# Sheet1.net
KiCad netlist of a schematic drawn in Altium Designer
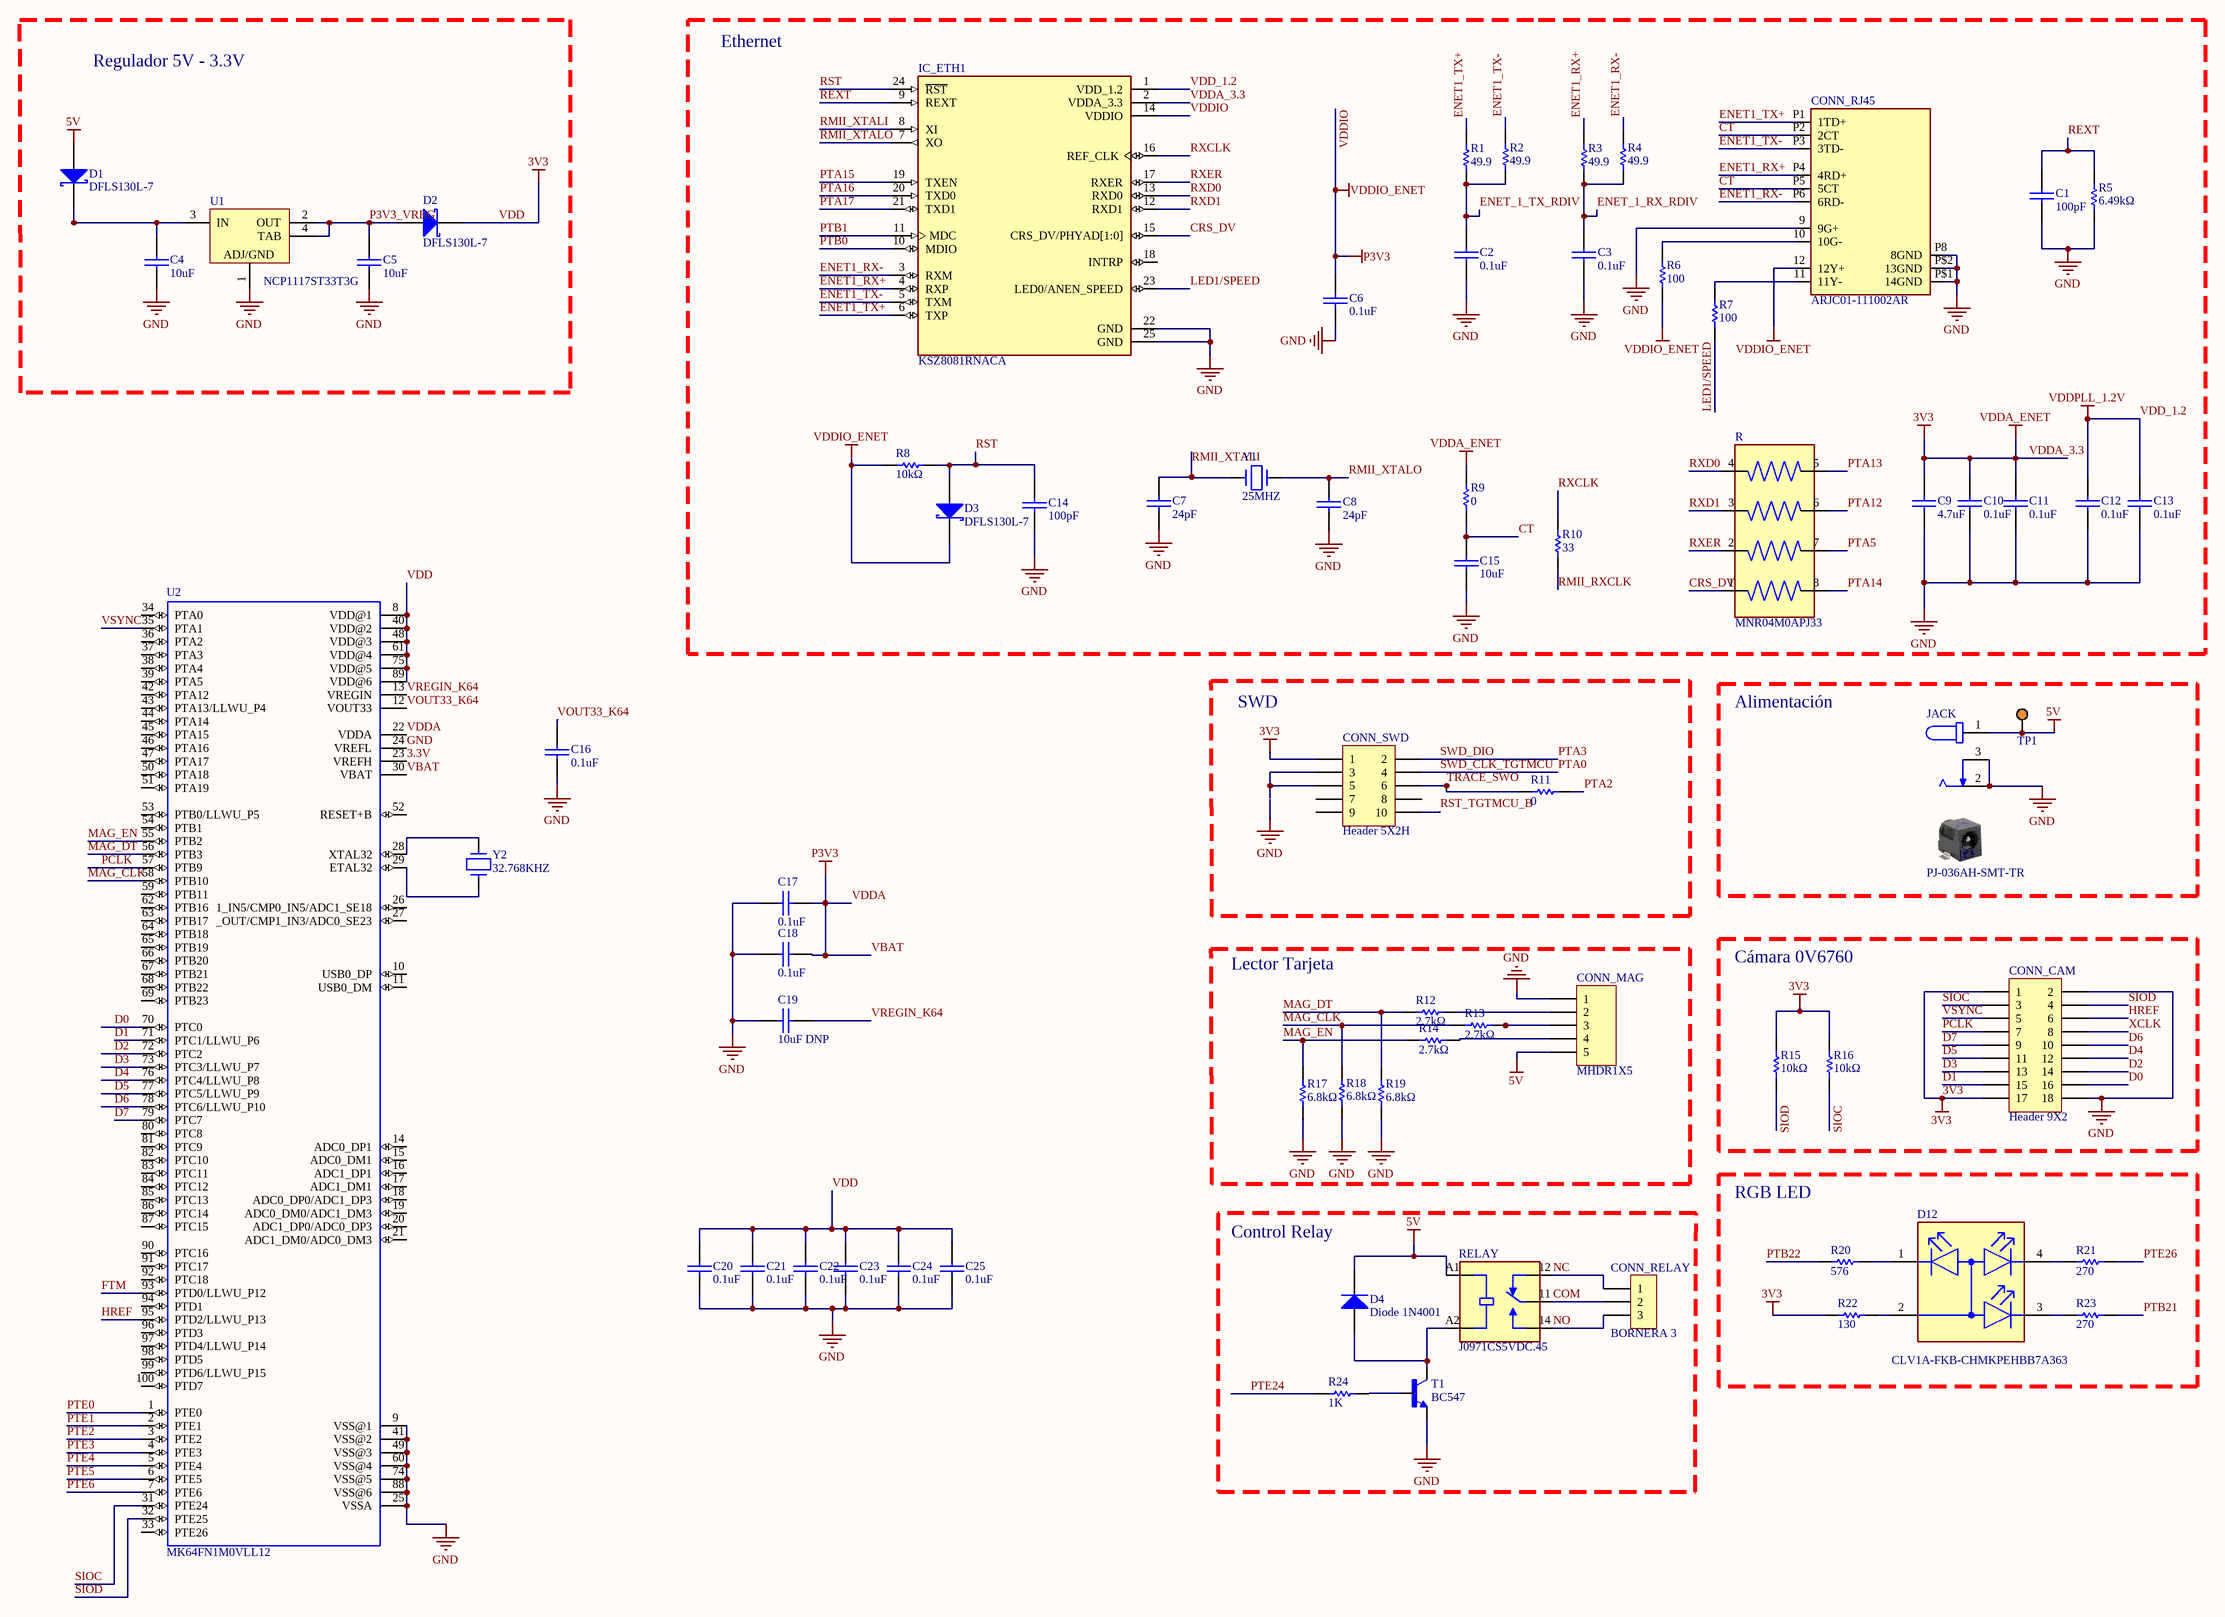
[diagram p0: Sheet1.SchDoc]

(export (version "E")
  (design (tool "Eeschema 10.0.6"))
  (components
    (comp (ref "C1") (value "100pF") (footprint "0805") (libsource (lib "Schematics") (part "CAP")))
    (comp (ref "C2") (value "0.1uF") (footprint "0805") (libsource (lib "Schematics") (part "CAP")))
    (comp (ref "C3") (value "0.1uF") (footprint "0805") (libsource (lib "Schematics") (part "CAP")))
    (comp (ref "C4") (value "10uF") (footprint "0805") (libsource (lib "Schematics") (part "CAP")))
    (comp (ref "C5") (value "10uF") (footprint "0805") (libsource (lib "Schematics") (part "CAP")))
    (comp (ref "C6") (value "0.1uF") (footprint "0805") (libsource (lib "Schematics") (part "CAP")))
    (comp (ref "C7") (value "24pF") (footprint "0805") (libsource (lib "Schematics") (part "CAP")))
    (comp (ref "C8") (value "24pF") (footprint "0805") (libsource (lib "Schematics") (part "CAP")))
    (comp (ref "C9") (value "4.7uF") (footprint "0805") (libsource (lib "Schematics") (part "CAP")))
    (comp (ref "C10") (value "0.1uF") (footprint "0805") (libsource (lib "Schematics") (part "CAP")))
    (comp (ref "C11") (value "0.1uF") (footprint "0805") (libsource (lib "Schematics") (part "CAP")))
    (comp (ref "C12") (value "0.1uF") (footprint "0805") (libsource (lib "Schematics") (part "CAP")))
    (comp (ref "C13") (value "0.1uF") (footprint "0805") (libsource (lib "Schematics") (part "CAP")))
    (comp (ref "C14") (value "100pF") (footprint "0805") (libsource (lib "Schematics") (part "CAP")))
    (comp (ref "C15") (value "10uF") (footprint "0805") (libsource (lib "Schematics") (part "CAP")))
    (comp (ref "C16") (value "0.1uF") (footprint "1206") (libsource (lib "Schematics") (part "CAP")))
    (comp (ref "C17") (value "0.1uF") (footprint "0805") (libsource (lib "Schematics") (part "CAP")))
    (comp (ref "C18") (value "0.1uF") (footprint "0805") (libsource (lib "Schematics") (part "CAP")))
    (comp (ref "C19") (value "10uF DNP") (footprint "1206") (libsource (lib "Schematics") (part "CAP")))
    (comp (ref "C20") (value "0.1uF") (footprint "0805") (libsource (lib "Schematics") (part "CAP")))
    (comp (ref "C21") (value "0.1uF") (footprint "0805") (libsource (lib "Schematics") (part "CAP")))
    (comp (ref "C22") (value "0.1uF") (footprint "0805") (libsource (lib "Schematics") (part "CAP")))
    (comp (ref "C23") (value "0.1uF") (footprint "0805") (libsource (lib "Schematics") (part "CAP")))
    (comp (ref "C24") (value "0.1uF") (footprint "0805") (libsource (lib "Schematics") (part "CAP")))
    (comp (ref "C25") (value "0.1uF") (footprint "0805") (libsource (lib "Schematics") (part "CAP")))
    (comp (ref "CONN_CAM")
      (value "Header 9X2")
      (footprint "HDR2X9")
      (description "Header, 9-Pin, Dual row")
      (fields (field (name "PUBLISHER") "Altium Limited"))
      (libsource (lib "Miscellaneous Connectors") (part "Header 9X2"))
    )
    (comp (ref "CONN_MAG")
      (value "MHDR1X5")
      (footprint "MHDR1X5")
      (description "Header, 5-Pin")
      (fields (field (name "PUBLISHER") "Altium Limited"))
      (libsource (lib "Miscellaneous Connectors") (part "MHDR1X5"))
    )
    (comp (ref "CONN_RELAY")
      (value "BORNERA 3")
      (footprint "BORNERA3")
      (libsource (lib "Schematics") (part "BORNERA 3"))
    )
    (comp (ref "CONN_RJ45")
      (value "ARJC01-111002AR")
      (footprint "ARJC01-111002AR")
      (description "1 Port RJ45 Magjack Connector Through Hole 10/100 Base-TX, AutoMDIX")
      (fields (field (name "MF") "Abracon LLC"))
      (libsource (lib "ARJC01-111002AR") (part "ARJC01-111002AR"))
    )
    (comp (ref "CONN_SWD")
      (value "Header 5X2H")
      (footprint "HDR2X5H")
      (description "Header, 5-Pin, Dual row, Right Angle")
      (fields (field (name "PUBLISHER") "Altium Limited"))
      (libsource (lib "Miscellaneous Connectors") (part "Header 5X2H"))
    )
    (comp (ref "D1")
      (value "DFLS130L-7")
      (footprint "DIOD-POWERDI123-2_A_V")
      (description "Schottky Barrier Rectifier, 30 V, 1 A, -40 to 125 degC, 2-Pin SMD, RoHS, Tape and Reel")
      (fields (field (name "MANUFACTURER") "Diodes Inc"))
      (libsource (lib "Altium Content Vault") (part "DSKY-AK-2"))
    )
    (comp (ref "D2")
      (value "DFLS130L-7")
      (footprint "DIOD-POWERDI123-2_A_V")
      (description "Schottky Barrier Rectifier, 30 V, 1 A, -40 to 125 degC, 2-Pin SMD, RoHS, Tape and Reel")
      (fields (field (name "MANUFACTURER") "Diodes Inc"))
      (libsource (lib "Altium Content Vault") (part "DSKY-AK-2"))
    )
    (comp (ref "D3")
      (value "DFLS130L-7")
      (footprint "DIOD-POWERDI123-2_A_V")
      (description "Schottky Barrier Rectifier, 30 V, 1 A, -40 to 125 degC, 2-Pin SMD, RoHS, Tape and Reel")
      (fields (field (name "MANUFACTURER") "Diodes Inc"))
      (libsource (lib "Altium Content Vault") (part "DSKY-AK-2"))
    )
    (comp (ref "D4")
      (value "Diode 1N4001")
      (footprint "DO-41")
      (description "1 Amp General Purpose Rectifier")
      (fields (field (name "PUBLISHER") "Altium Limited"))
      (libsource (lib "Miscellaneous Devices") (part "Diode 1N4001"))
    )
    (comp (ref "D12")
      (value "CLV1A-FKB-CHMKPEHBB7A363")
      (footprint "FP-CLV1A-FKB-CHMKPEHBB7A3-MFG")
      (description "LED RGB 4PLCC SMD")
      (libsource (lib "Altium Content Vault") (part "37e83e7cb408f3cd33eae76522c4c17"))
    )
    (comp (ref "IC_ETH1")
      (value "KSZ8081RNACA")
      (footprint "QFN50P400X400X90-25N")
      (description "1/1 Transceiver Full RMII 24-QFN _4x4_")
      (fields (field (name "MF") "Microchip"))
      (libsource (lib "KSZ8081RNACA") (part "KSZ8081RNACA"))
    )
    (comp (ref "JACK")
      (value "CONN_JACKDC_SMD_PJ-036AH-SMT-TR")
      (footprint "CUI_PJ-036AH-SMT-TR")
      (description "CONN PWR JACK 2X5.5MM SOLDER")
      (fields
        (field (name "MANUFACTURER") "CUI Devices")
        (field (name "MANUFACTURER PART NUMBER") "PJ-036AH-SMT-TR")
      )
      (libsource (lib "NerveBox") (part "CONN_JACKDC_SMD_PJ-036AH-SMT-TR"))
    )
    (comp (ref "R")
      (value "MNR04M0APJ33")
      (footprint "RESCAXS50P200X100X45-8N")
      (description "Res Array 330K Ohm 5% Â±200ppm/Â°C ISOL Epoxy 8-Pin 0804(4 X 0402) Convex SMD Automotive T/R")
      (fields (field (name "MP") "MNR04M0APJ334") (field (name "MF") "Rohm"))
      (libsource (lib "MNR04M0APJ334") (part "MNR04M0APJ334"))
    )
    (comp (ref "R1") (value "49.9") (footprint "0805") (libsource (lib "Schematics") (part "RES")))
    (comp (ref "R2") (value "49.9") (footprint "0805") (libsource (lib "Schematics") (part "RES")))
    (comp (ref "R3") (value "49.9") (footprint "0805") (libsource (lib "Schematics") (part "RES")))
    (comp (ref "R4") (value "49.9") (footprint "0805") (libsource (lib "Schematics") (part "RES")))
    (comp (ref "R5")
      (value "RES_10k_SMD_RMCF0603FT10K0")
      (footprint "RES_0603")
      (description "RES 10K OHM 1% 1/10W 0603")
      (fields
        (field (name "MANUFACTURER PART NUMBER") "RMCF0603FT10K0")
        (field (name "MANUFACTURER") "Stackpole Electronics Inc")
        (field (name "POWER") "6.49kΩ")
      )
      (libsource (lib "NerveBox") (part "RES_10k_SMD_RMCF0603FT10K0"))
    )
    (comp (ref "R6") (value "100") (footprint "0805") (libsource (lib "Schematics") (part "RES")))
    (comp (ref "R7") (value "100") (footprint "0805") (libsource (lib "Schematics") (part "RES")))
    (comp (ref "R8")
      (value "RES_10k_SMD_RMCF0603FT10K0")
      (footprint "RES_0603")
      (description "RES 10K OHM 1% 1/10W 0603")
      (fields
        (field (name "MANUFACTURER PART NUMBER") "RMCF0603FT10K0")
        (field (name "MANUFACTURER") "Stackpole Electronics Inc")
        (field (name "POWER") "10kΩ")
      )
      (libsource (lib "NerveBox") (part "RES_10k_SMD_RMCF0603FT10K0"))
    )
    (comp (ref "R9") (value "0") (footprint "0805") (libsource (lib "Schematics") (part "RES")))
    (comp (ref "R10")
      (value "RES_10k_SMD_RMCF0603FT10K0")
      (footprint "RES_0603")
      (description "RES 10K OHM 1% 1/10W 0603")
      (fields
        (field (name "MANUFACTURER PART NUMBER") "RMCF0603FT10K0")
        (field (name "MANUFACTURER") "Stackpole Electronics Inc")
        (field (name "POWER") "33")
      )
      (libsource (lib "NerveBox") (part "RES_10k_SMD_RMCF0603FT10K0"))
    )
    (comp (ref "R11")
      (value "RES_10k_SMD_RMCF0603FT10K0")
      (footprint "RES_0603")
      (description "RES 10K OHM 1% 1/10W 0603")
      (fields
        (field (name "MANUFACTURER PART NUMBER") "RMCF0603FT10K0")
        (field (name "MANUFACTURER") "Stackpole Electronics Inc")
        (field (name "POWER") "0")
      )
      (libsource (lib "NerveBox") (part "RES_10k_SMD_RMCF0603FT10K0"))
    )
    (comp (ref "R12")
      (value "RES_10k_SMD_RMCF0603FT10K0")
      (footprint "RES_0603")
      (description "RES 10K OHM 1% 1/10W 0603")
      (fields
        (field (name "MANUFACTURER PART NUMBER") "RMCF0603FT10K0")
        (field (name "MANUFACTURER") "Stackpole Electronics Inc")
        (field (name "POWER") "2.7kΩ")
      )
      (libsource (lib "NerveBox") (part "RES_10k_SMD_RMCF0603FT10K0"))
    )
    (comp (ref "R13")
      (value "RES_10k_SMD_RMCF0603FT10K0")
      (footprint "RES_0603")
      (description "RES 10K OHM 1% 1/10W 0603")
      (fields
        (field (name "MANUFACTURER PART NUMBER") "RMCF0603FT10K0")
        (field (name "MANUFACTURER") "Stackpole Electronics Inc")
        (field (name "POWER") "2.7kΩ")
      )
      (libsource (lib "NerveBox") (part "RES_10k_SMD_RMCF0603FT10K0"))
    )
    (comp (ref "R14")
      (value "RES_10k_SMD_RMCF0603FT10K0")
      (footprint "RES_0603")
      (description "RES 10K OHM 1% 1/10W 0603")
      (fields
        (field (name "MANUFACTURER PART NUMBER") "RMCF0603FT10K0")
        (field (name "MANUFACTURER") "Stackpole Electronics Inc")
        (field (name "POWER") "2.7kΩ")
      )
      (libsource (lib "NerveBox") (part "RES_10k_SMD_RMCF0603FT10K0"))
    )
    (comp (ref "R15")
      (value "RES_10k_SMD_RMCF0603FT10K0")
      (footprint "RES_0603")
      (description "RES 10K OHM 1% 1/10W 0603")
      (fields
        (field (name "MANUFACTURER PART NUMBER") "RMCF0603FT10K0")
        (field (name "MANUFACTURER") "Stackpole Electronics Inc")
        (field (name "POWER") "10kΩ")
      )
      (libsource (lib "NerveBox") (part "RES_10k_SMD_RMCF0603FT10K0"))
    )
    (comp (ref "R16")
      (value "RES_10k_SMD_RMCF0603FT10K0")
      (footprint "RES_0603")
      (description "RES 10K OHM 1% 1/10W 0603")
      (fields
        (field (name "MANUFACTURER PART NUMBER") "RMCF0603FT10K0")
        (field (name "MANUFACTURER") "Stackpole Electronics Inc")
        (field (name "POWER") "10kΩ")
      )
      (libsource (lib "NerveBox") (part "RES_10k_SMD_RMCF0603FT10K0"))
    )
    (comp (ref "R17")
      (value "RES_10k_SMD_RMCF0603FT10K0")
      (footprint "RES_0603")
      (description "RES 10K OHM 1% 1/10W 0603")
      (fields
        (field (name "MANUFACTURER PART NUMBER") "RMCF0603FT10K0")
        (field (name "MANUFACTURER") "Stackpole Electronics Inc")
        (field (name "POWER") "6.8kΩ")
      )
      (libsource (lib "NerveBox") (part "RES_10k_SMD_RMCF0603FT10K0"))
    )
    (comp (ref "R18")
      (value "RES_10k_SMD_RMCF0603FT10K0")
      (footprint "RES_0603")
      (description "RES 10K OHM 1% 1/10W 0603")
      (fields
        (field (name "MANUFACTURER PART NUMBER") "RMCF0603FT10K0")
        (field (name "MANUFACTURER") "Stackpole Electronics Inc")
        (field (name "POWER") "6.8kΩ")
      )
      (libsource (lib "NerveBox") (part "RES_10k_SMD_RMCF0603FT10K0"))
    )
    (comp (ref "R19")
      (value "RES_10k_SMD_RMCF0603FT10K0")
      (footprint "RES_0603")
      (description "RES 10K OHM 1% 1/10W 0603")
      (fields
        (field (name "MANUFACTURER PART NUMBER") "RMCF0603FT10K0")
        (field (name "MANUFACTURER") "Stackpole Electronics Inc")
        (field (name "POWER") "6.8kΩ")
      )
      (libsource (lib "NerveBox") (part "RES_10k_SMD_RMCF0603FT10K0"))
    )
    (comp (ref "R20")
      (value "RES_10k_SMD_RMCF0603FT10K0")
      (footprint "RES_0603")
      (description "RES 10K OHM 1% 1/10W 0603")
      (fields
        (field (name "MANUFACTURER PART NUMBER") "RMCF0603FT10K0")
        (field (name "MANUFACTURER") "Stackpole Electronics Inc")
        (field (name "POWER") "576")
      )
      (libsource (lib "NerveBox") (part "RES_10k_SMD_RMCF0603FT10K0"))
    )
    (comp (ref "R21")
      (value "RES_10k_SMD_RMCF0603FT10K0")
      (footprint "RES_0603")
      (description "RES 10K OHM 1% 1/10W 0603")
      (fields
        (field (name "MANUFACTURER PART NUMBER") "RMCF0603FT10K0")
        (field (name "MANUFACTURER") "Stackpole Electronics Inc")
        (field (name "POWER") "270")
      )
      (libsource (lib "NerveBox") (part "RES_10k_SMD_RMCF0603FT10K0"))
    )
    (comp (ref "R22")
      (value "RES_10k_SMD_RMCF0603FT10K0")
      (footprint "RES_0603")
      (description "RES 10K OHM 1% 1/10W 0603")
      (fields
        (field (name "MANUFACTURER PART NUMBER") "RMCF0603FT10K0")
        (field (name "MANUFACTURER") "Stackpole Electronics Inc")
        (field (name "POWER") "130")
      )
      (libsource (lib "NerveBox") (part "RES_10k_SMD_RMCF0603FT10K0"))
    )
    (comp (ref "R23")
      (value "RES_10k_SMD_RMCF0603FT10K0")
      (footprint "RES_0603")
      (description "RES 10K OHM 1% 1/10W 0603")
      (fields
        (field (name "MANUFACTURER PART NUMBER") "RMCF0603FT10K0")
        (field (name "MANUFACTURER") "Stackpole Electronics Inc")
        (field (name "POWER") "270")
      )
      (libsource (lib "NerveBox") (part "RES_10k_SMD_RMCF0603FT10K0"))
    )
    (comp (ref "R24") (value "1K") (footprint "0805") (libsource (lib "Schematics") (part "RES")))
    (comp (ref "RELAY")
      (value "J0971CS5VDC.45")
      (footprint "RELAY_J0971CS5VDC.45")
      (description "General Purpose Relay SPDT (1 Form C) 5VDC Coil Through Hole")
      (fields (field (name "MF") "CIT Relay and Switch"))
      (libsource (lib "J0971CS5VDC.45") (part "J0971CS5VDC.45"))
    )
    (comp (ref "T1")
      (value "BC547")
      (footprint "TO92")
      (description "Trans GP BJT NPN 45V 0.1A 500mW 3-Pin TO-92 T/R")
      (fields (field (name "MF") "ON Semiconductor"))
      (libsource (lib "BC547") (part "BC547"))
    )
    (comp (ref "TP1")
      (value "MISC_TESTPOINT")
      (footprint "TP_SIGNAL")
      (description "TESTPOINT")
      (libsource (lib "NerveBox") (part "MISC_TP"))
    )
    (comp (ref "U1")
      (value "NCP1117ST33T3G")
      (footprint "ONSC-SOT-223-4-318H-01_A_V")
      (fields (field (name "TOLERANCE") "1%"))
      (libsource (lib "Altium Content Vault") (part "ONSC-NCP1117-SOT223-4"))
    )
    (comp (ref "U2")
      (value "MK64FN1M0VLL12")
      (footprint "QFP50P1600X1600X170-100N")
      (description "ARMÂ® CortexÂ®-M4 Kinetis K60 Microcontroller IC 32-Bit 120MHz 1MB _1M x 8_ FLASH 100-LQFP _14x14_")
      (fields (field (name "MF") "NXP USA"))
      (libsource (lib "MK64FN1M0VLL12") (part "MK64FN1M0VLL12"))
    )
    (comp (ref "Y1")
      (value "25MHZ")
      (footprint "CRISTAL PERFIL")
      (libsource (lib "Schematics") (part "CRISTAL"))
    )
    (comp (ref "Y2")
      (value "32.768KHZ")
      (footprint "CRISTAL PERFIL")
      (libsource (lib "Schematics") (part "CRISTAL"))
    )
  )
  (nets
    (net (code "1") (name "/3.3V") (class "Default")
      (node (ref "U2") (pin "23") (pinfunction "VREFH_23") (pintype "power_in"))
    )
    (net (code "2") (name "/COM") (class "Default")
      (node (ref "CONN_RELAY") (pin "2") (pinfunction "2_2") (pintype "passive"))
      (node (ref "RELAY") (pin "11") (pinfunction "COM_11") (pintype "passive"))
    )
    (net (code "3") (name "/CRS_DV") (class "Default")
      (node (ref "IC_ETH1") (pin "15") (pinfunction "CRS_DV/PHYAD[1:0]_15") (pintype "bidirectional"))
      (node (ref "R") (pin "1") (pinfunction "1_1") (pintype "passive"))
    )
    (net (code "4") (name "/CT") (class "Default")
      (node (ref "C15") (pin "2") (pinfunction "2_2") (pintype "passive"))
      (node (ref "CONN_RJ45") (pin "P2") (pinfunction "2CT_P2") (pintype "passive"))
      (node (ref "CONN_RJ45") (pin "P5") (pinfunction "5CT_P5") (pintype "passive"))
      (node (ref "R9") (pin "1") (pinfunction "1_1") (pintype "passive"))
    )
    (net (code "5") (name "/D0") (class "Default")
      (node (ref "CONN_CAM") (pin "16") (pinfunction "16_16") (pintype "passive"))
      (node (ref "U2") (pin "70") (pinfunction "PTC0_70") (pintype "bidirectional"))
    )
    (net (code "6") (name "/D1") (class "Default")
      (node (ref "CONN_CAM") (pin "15") (pinfunction "15_15") (pintype "passive"))
      (node (ref "U2") (pin "71") (pinfunction "PTC1/LLWU_P6_71") (pintype "bidirectional"))
    )
    (net (code "7") (name "/D2") (class "Default")
      (node (ref "CONN_CAM") (pin "14") (pinfunction "14_14") (pintype "passive"))
      (node (ref "U2") (pin "72") (pinfunction "PTC2_72") (pintype "bidirectional"))
    )
    (net (code "8") (name "/D3") (class "Default")
      (node (ref "CONN_CAM") (pin "13") (pinfunction "13_13") (pintype "passive"))
      (node (ref "U2") (pin "73") (pinfunction "PTC3/LLWU_P7_73") (pintype "bidirectional"))
    )
    (net (code "9") (name "/D4") (class "Default")
      (node (ref "CONN_CAM") (pin "12") (pinfunction "12_12") (pintype "passive"))
      (node (ref "U2") (pin "76") (pinfunction "PTC4/LLWU_P8_76") (pintype "bidirectional"))
    )
    (net (code "10") (name "/D5") (class "Default")
      (node (ref "CONN_CAM") (pin "11") (pinfunction "11_11") (pintype "passive"))
      (node (ref "U2") (pin "77") (pinfunction "PTC5/LLWU_P9_77") (pintype "bidirectional"))
    )
    (net (code "11") (name "/D6") (class "Default")
      (node (ref "CONN_CAM") (pin "10") (pinfunction "10_10") (pintype "passive"))
      (node (ref "U2") (pin "78") (pinfunction "PTC6/LLWU_P10_78") (pintype "bidirectional"))
    )
    (net (code "12") (name "/D7") (class "Default")
      (node (ref "CONN_CAM") (pin "9") (pinfunction "9_9") (pintype "passive"))
      (node (ref "U2") (pin "79") (pinfunction "PTC7_79") (pintype "bidirectional"))
    )
    (net (code "13") (name "/ENET1_RX+") (class "Default")
      (node (ref "CONN_RJ45") (pin "P4") (pinfunction "4RD+_P4") (pintype "passive"))
      (node (ref "IC_ETH1") (pin "4") (pinfunction "RXP_4") (pintype "bidirectional"))
      (node (ref "R3") (pin "2") (pinfunction "2_2") (pintype "passive"))
    )
    (net (code "14") (name "/ENET1_RX-") (class "Default")
      (node (ref "CONN_RJ45") (pin "P6") (pinfunction "6RD-_P6") (pintype "passive"))
      (node (ref "IC_ETH1") (pin "3") (pinfunction "RXM_3") (pintype "bidirectional"))
      (node (ref "R4") (pin "2") (pinfunction "2_2") (pintype "passive"))
    )
    (net (code "15") (name "/ENET1_TX+") (class "Default")
      (node (ref "CONN_RJ45") (pin "P1") (pinfunction "1TD+_P1") (pintype "passive"))
      (node (ref "IC_ETH1") (pin "6") (pinfunction "TXP_6") (pintype "bidirectional"))
      (node (ref "R1") (pin "2") (pinfunction "2_2") (pintype "passive"))
    )
    (net (code "16") (name "/ENET1_TX-") (class "Default")
      (node (ref "CONN_RJ45") (pin "P3") (pinfunction "3TD-_P3") (pintype "passive"))
      (node (ref "IC_ETH1") (pin "5") (pinfunction "TXM_5") (pintype "bidirectional"))
      (node (ref "R2") (pin "2") (pinfunction "2_2") (pintype "passive"))
    )
    (net (code "17") (name "/ENET_1_RX_RDIV") (class "Default")
      (node (ref "C3") (pin "2") (pinfunction "2_2") (pintype "passive"))
      (node (ref "R3") (pin "1") (pinfunction "1_1") (pintype "passive"))
      (node (ref "R4") (pin "1") (pinfunction "1_1") (pintype "passive"))
    )
    (net (code "18") (name "/ENET_1_TX_RDIV") (class "Default")
      (node (ref "C2") (pin "2") (pinfunction "2_2") (pintype "passive"))
      (node (ref "R1") (pin "1") (pinfunction "1_1") (pintype "passive"))
      (node (ref "R2") (pin "1") (pinfunction "1_1") (pintype "passive"))
    )
    (net (code "19") (name "/FTM") (class "Default")
      (node (ref "U2") (pin "93") (pinfunction "PTD0/LLWU_P12_93") (pintype "bidirectional"))
    )
    (net (code "20") (name "/HREF") (class "Default")
      (node (ref "CONN_CAM") (pin "6") (pinfunction "6_6") (pintype "passive"))
      (node (ref "U2") (pin "95") (pinfunction "PTD2/LLWU_P13_95") (pintype "bidirectional"))
    )
    (net (code "21") (name "/LED1{slash}SPEED") (class "Default")
      (node (ref "IC_ETH1") (pin "23") (pinfunction "LED0/ANEN_SPEED_23") (pintype "bidirectional"))
      (node (ref "R7") (pin "1") (pinfunction "1_1") (pintype "passive"))
    )
    (net (code "22") (name "/MAG_CLK") (class "Default")
      (node (ref "R13") (pin "2") (pinfunction "2_2") (pintype "passive"))
      (node (ref "R18") (pin "1") (pinfunction "1_1") (pintype "passive"))
      (node (ref "U2") (pin "58") (pinfunction "PTB10_58") (pintype "bidirectional"))
    )
    (net (code "23") (name "/MAG_DT") (class "Default")
      (node (ref "R12") (pin "2") (pinfunction "2_2") (pintype "passive"))
      (node (ref "R19") (pin "1") (pinfunction "1_1") (pintype "passive"))
      (node (ref "U2") (pin "56") (pinfunction "PTB3_56") (pintype "bidirectional"))
    )
    (net (code "24") (name "/MAG_EN") (class "Default")
      (node (ref "R14") (pin "1") (pinfunction "1_1") (pintype "passive"))
      (node (ref "R17") (pin "1") (pinfunction "1_1") (pintype "passive"))
      (node (ref "U2") (pin "55") (pinfunction "PTB2_55") (pintype "bidirectional"))
    )
    (net (code "25") (name "/NC") (class "Default")
      (node (ref "CONN_RELAY") (pin "1") (pinfunction "1_1") (pintype "passive"))
      (node (ref "RELAY") (pin "12") (pinfunction "NC_12") (pintype "passive"))
    )
    (net (code "26") (name "/NO") (class "Default")
      (node (ref "CONN_RELAY") (pin "3") (pinfunction "3_3") (pintype "passive"))
      (node (ref "RELAY") (pin "14") (pinfunction "NO_14") (pintype "passive"))
    )
    (net (code "27") (name "/P3V3_VREG") (class "Default")
      (node (ref "C5") (pin "1") (pinfunction "1_1") (pintype "passive"))
      (node (ref "D2") (pin "1") (pinfunction "A_1") (pintype "passive"))
      (node (ref "U1") (pin "2") (pinfunction "OUT_2") (pintype "power_in"))
      (node (ref "U1") (pin "4") (pinfunction "TAB_4") (pintype "passive"))
    )
    (net (code "28") (name "/PCLK") (class "Default")
      (node (ref "CONN_CAM") (pin "7") (pinfunction "7_7") (pintype "passive"))
      (node (ref "U2") (pin "57") (pinfunction "PTB9_57") (pintype "bidirectional"))
    )
    (net (code "29") (name "/PTA0") (class "Default")
      (node (ref "CONN_SWD") (pin "4") (pinfunction "4_4") (pintype "passive"))
    )
    (net (code "30") (name "/PTA2") (class "Default")
      (node (ref "R11") (pin "1") (pinfunction "1_1") (pintype "passive"))
    )
    (net (code "31") (name "/PTA3") (class "Default")
      (node (ref "CONN_SWD") (pin "2") (pinfunction "2_2") (pintype "passive"))
    )
    (net (code "32") (name "/PTA5") (class "Default")
      (node (ref "R") (pin "7") (pinfunction "7_7") (pintype "passive"))
    )
    (net (code "33") (name "/PTA12") (class "Default")
      (node (ref "R") (pin "6") (pinfunction "6_6") (pintype "passive"))
    )
    (net (code "34") (name "/PTA13") (class "Default")
      (node (ref "R") (pin "5") (pinfunction "5_5") (pintype "passive"))
    )
    (net (code "35") (name "/PTA14") (class "Default")
      (node (ref "R") (pin "8") (pinfunction "8_8") (pintype "passive"))
    )
    (net (code "36") (name "/PTA15") (class "Default")
      (node (ref "IC_ETH1") (pin "19") (pinfunction "TXEN_19") (pintype "input"))
    )
    (net (code "37") (name "/PTA16") (class "Default")
      (node (ref "IC_ETH1") (pin "20") (pinfunction "TXD0_20") (pintype "input"))
    )
    (net (code "38") (name "/PTA17") (class "Default")
      (node (ref "IC_ETH1") (pin "21") (pinfunction "TXD1_21") (pintype "bidirectional"))
    )
    (net (code "39") (name "/PTB0") (class "Default")
      (node (ref "IC_ETH1") (pin "10") (pinfunction "MDIO_10") (pintype "bidirectional"))
    )
    (net (code "40") (name "/PTB1") (class "Default")
      (node (ref "IC_ETH1") (pin "11") (pinfunction "MDC_11") (pintype "input"))
    )
    (net (code "41") (name "/PTB21") (class "Default")
      (node (ref "R23") (pin "2") (pinfunction "2_2") (pintype "passive"))
    )
    (net (code "42") (name "/PTB22") (class "Default")
      (node (ref "R20") (pin "2") (pinfunction "2_2") (pintype "passive"))
    )
    (net (code "43") (name "/PTE0") (class "Default")
      (node (ref "U2") (pin "1") (pinfunction "PTE0_1") (pintype "bidirectional"))
    )
    (net (code "45") (name "/PTE1") (class "Default")
      (node (ref "U2") (pin "2") (pinfunction "PTE1_2") (pintype "bidirectional"))
    )
    (net (code "46") (name "/PTE2") (class "Default")
      (node (ref "U2") (pin "3") (pinfunction "PTE2_3") (pintype "bidirectional"))
    )
    (net (code "47") (name "/PTE3") (class "Default")
      (node (ref "U2") (pin "4") (pinfunction "PTE3_4") (pintype "bidirectional"))
    )
    (net (code "48") (name "/PTE4") (class "Default")
      (node (ref "U2") (pin "5") (pinfunction "PTE4_5") (pintype "bidirectional"))
    )
    (net (code "49") (name "/PTE5") (class "Default")
      (node (ref "U2") (pin "6") (pinfunction "PTE5_6") (pintype "bidirectional"))
    )
    (net (code "50") (name "/PTE6") (class "Default")
      (node (ref "U2") (pin "7") (pinfunction "PTE6_7") (pintype "bidirectional"))
    )
    (net (code "51") (name "/PTE24") (class "Default")
      (node (ref "R24") (pin "2") (pinfunction "2_2") (pintype "passive"))
    )
    (net (code "52") (name "/PTE26") (class "Default")
      (node (ref "R21") (pin "2") (pinfunction "2_2") (pintype "passive"))
    )
    (net (code "53") (name "/REXT") (class "Default")
      (node (ref "C1") (pin "1") (pinfunction "1_1") (pintype "passive"))
      (node (ref "IC_ETH1") (pin "9") (pinfunction "REXT_9") (pintype "input"))
      (node (ref "R5") (pin "1") (pinfunction "1_1") (pintype "passive"))
    )
    (net (code "54") (name "/RMII_RXCLK") (class "Default")
      (node (ref "R10") (pin "2") (pinfunction "2_2") (pintype "passive"))
    )
    (net (code "55") (name "/RMII_XTALI") (class "Default")
      (node (ref "C7") (pin "1") (pinfunction "1_1") (pintype "passive"))
      (node (ref "IC_ETH1") (pin "8") (pinfunction "XI_8") (pintype "input"))
      (node (ref "Y1") (pin "2") (pinfunction "10_2") (pintype "passive"))
    )
    (net (code "56") (name "/RMII_XTALO") (class "Default")
      (node (ref "C8") (pin "1") (pinfunction "1_1") (pintype "passive"))
      (node (ref "IC_ETH1") (pin "7") (pinfunction "XO_7") (pintype "output"))
      (node (ref "Y1") (pin "1") (pinfunction "1_1") (pintype "passive"))
    )
    (net (code "57") (name "/RST") (class "Default")
      (node (ref "C14") (pin "2") (pinfunction "2_2") (pintype "passive"))
      (node (ref "D3") (pin "1") (pinfunction "A_1") (pintype "passive"))
      (node (ref "IC_ETH1") (pin "24") (pinfunction "~{RST}_24") (pintype "input"))
      (node (ref "R8") (pin "1") (pinfunction "1_1") (pintype "passive"))
    )
    (net (code "58") (name "/RST_TGTMCU_B") (class "Default")
      (node (ref "CONN_SWD") (pin "10") (pinfunction "10_10") (pintype "passive"))
    )
    (net (code "59") (name "/RXCLK") (class "Default")
      (node (ref "IC_ETH1") (pin "16") (pinfunction "REF_CLK_16") (pintype "bidirectional"))
      (node (ref "R10") (pin "1") (pinfunction "1_1") (pintype "passive"))
    )
    (net (code "60") (name "/RXD0") (class "Default")
      (node (ref "IC_ETH1") (pin "13") (pinfunction "RXD0_13") (pintype "bidirectional"))
      (node (ref "R") (pin "4") (pinfunction "4_4") (pintype "passive"))
    )
    (net (code "61") (name "/RXD1") (class "Default")
      (node (ref "IC_ETH1") (pin "12") (pinfunction "RXD1_12") (pintype "bidirectional"))
      (node (ref "R") (pin "3") (pinfunction "3_3") (pintype "passive"))
    )
    (net (code "62") (name "/RXER") (class "Default")
      (node (ref "IC_ETH1") (pin "17") (pinfunction "RXER_17") (pintype "bidirectional"))
      (node (ref "R") (pin "2") (pinfunction "2_2") (pintype "passive"))
    )
    (net (code "63") (name "/SIOC") (class "Default")
      (node (ref "CONN_CAM") (pin "3") (pinfunction "3_3") (pintype "passive"))
      (node (ref "R16") (pin "1") (pinfunction "1_1") (pintype "passive"))
      (node (ref "U2") (pin "31") (pinfunction "PTE24_31") (pintype "bidirectional"))
    )
    (net (code "64") (name "/SIOD") (class "Default")
      (node (ref "CONN_CAM") (pin "4") (pinfunction "4_4") (pintype "passive"))
      (node (ref "R15") (pin "1") (pinfunction "1_1") (pintype "passive"))
      (node (ref "U2") (pin "32") (pinfunction "PTE25_32") (pintype "bidirectional"))
    )
    (net (code "65") (name "/TRACE_SWO") (class "Default")
      (node (ref "CONN_SWD") (pin "6") (pinfunction "6_6") (pintype "passive"))
      (node (ref "R11") (pin "2") (pinfunction "2_2") (pintype "passive"))
    )
    (net (code "66") (name "/VOUT33_K64") (class "Default")
      (node (ref "C16") (pin "2") (pinfunction "2_2") (pintype "passive"))
      (node (ref "U2") (pin "12") (pinfunction "VOUT33_12") (pintype "power_in"))
    )
    (net (code "67") (name "/VREGIN_K64") (class "Default")
      (node (ref "C19") (pin "1") (pinfunction "1_1") (pintype "passive"))
      (node (ref "U2") (pin "13") (pinfunction "VREGIN_13") (pintype "power_in"))
    )
    (net (code "68") (name "/VSYNC") (class "Default")
      (node (ref "CONN_CAM") (pin "5") (pinfunction "5_5") (pintype "passive"))
      (node (ref "U2") (pin "35") (pinfunction "PTA1_35") (pintype "bidirectional"))
    )
    (net (code "69") (name "/XCLK") (class "Default")
      (node (ref "CONN_CAM") (pin "8") (pinfunction "8_8") (pintype "passive"))
    )
    (net (code "70") (name "3V3") (class "Default")
      (node (ref "C10") (pin "1") (pinfunction "1_1") (pintype "passive"))
      (node (ref "C11") (pin "1") (pinfunction "1_1") (pintype "passive"))
      (node (ref "C20") (pin "2") (pinfunction "2_2") (pintype "passive"))
      (node (ref "C21") (pin "2") (pinfunction "2_2") (pintype "passive"))
      (node (ref "C22") (pin "2") (pinfunction "2_2") (pintype "passive"))
      (node (ref "C23") (pin "2") (pinfunction "2_2") (pintype "passive"))
      (node (ref "C24") (pin "2") (pinfunction "2_2") (pintype "passive"))
      (node (ref "C25") (pin "2") (pinfunction "2_2") (pintype "passive"))
      (node (ref "C9") (pin "1") (pinfunction "1_1") (pintype "passive"))
      (node (ref "CONN_CAM") (pin "1") (pinfunction "1_1") (pintype "passive"))
      (node (ref "CONN_CAM") (pin "17") (pinfunction "17_17") (pintype "passive"))
      (node (ref "CONN_SWD") (pin "1") (pinfunction "1_1") (pintype "passive"))
      (node (ref "D2") (pin "2") (pinfunction "K_2") (pintype "passive"))
      (node (ref "IC_ETH1") (pin "2") (pinfunction "VDDA_3.3_2") (pintype "power_in"))
      (node (ref "R15") (pin "2") (pinfunction "2_2") (pintype "passive"))
      (node (ref "R16") (pin "2") (pinfunction "2_2") (pintype "passive"))
      (node (ref "R22") (pin "2") (pinfunction "2_2") (pintype "passive"))
      (node (ref "R9") (pin "2") (pinfunction "2_2") (pintype "passive"))
      (node (ref "U2") (pin "40") (pinfunction "VDD@2_40") (pintype "power_in"))
      (node (ref "U2") (pin "48") (pinfunction "VDD@3_48") (pintype "power_in"))
      (node (ref "U2") (pin "61") (pinfunction "VDD@4_61") (pintype "power_in"))
      (node (ref "U2") (pin "75") (pinfunction "VDD@5_75") (pintype "power_in"))
      (node (ref "U2") (pin "8") (pinfunction "VDD@1_8") (pintype "power_in"))
      (node (ref "U2") (pin "89") (pinfunction "VDD@6_89") (pintype "power_in"))
    )
    (net (code "71") (name "5V") (class "Default")
      (node (ref "CONN_MAG") (pin "5") (pinfunction "5_5") (pintype "passive"))
      (node (ref "D1") (pin "1") (pinfunction "A_1") (pintype "passive"))
      (node (ref "D4") (pin "2") (pinfunction "K_2") (pintype "passive"))
      (node (ref "JACK") (pin "1") (pinfunction "1_1") (pintype "passive"))
      (node (ref "RELAY") (pin "A1") (pinfunction "COIL1_A1") (pintype "passive"))
      (node (ref "TP1") (pin "1") (pinfunction "34_1") (pintype "passive"))
    )
    (net (code "72") (name "GND") (class "Default")
      (node (ref "C1") (pin "2") (pinfunction "2_2") (pintype "passive"))
      (node (ref "C10") (pin "2") (pinfunction "2_2") (pintype "passive"))
      (node (ref "C11") (pin "2") (pinfunction "2_2") (pintype "passive"))
      (node (ref "C12") (pin "2") (pinfunction "2_2") (pintype "passive"))
      (node (ref "C13") (pin "2") (pinfunction "2_2") (pintype "passive"))
      (node (ref "C14") (pin "1") (pinfunction "1_1") (pintype "passive"))
      (node (ref "C15") (pin "1") (pinfunction "1_1") (pintype "passive"))
      (node (ref "C16") (pin "1") (pinfunction "1_1") (pintype "passive"))
      (node (ref "C17") (pin "1") (pinfunction "1_1") (pintype "passive"))
      (node (ref "C18") (pin "1") (pinfunction "1_1") (pintype "passive"))
      (node (ref "C19") (pin "2") (pinfunction "2_2") (pintype "passive"))
      (node (ref "C2") (pin "1") (pinfunction "1_1") (pintype "passive"))
      (node (ref "C20") (pin "1") (pinfunction "1_1") (pintype "passive"))
      (node (ref "C21") (pin "1") (pinfunction "1_1") (pintype "passive"))
      (node (ref "C22") (pin "1") (pinfunction "1_1") (pintype "passive"))
      (node (ref "C23") (pin "1") (pinfunction "1_1") (pintype "passive"))
      (node (ref "C24") (pin "1") (pinfunction "1_1") (pintype "passive"))
      (node (ref "C25") (pin "1") (pinfunction "1_1") (pintype "passive"))
      (node (ref "C3") (pin "1") (pinfunction "1_1") (pintype "passive"))
      (node (ref "C4") (pin "2") (pinfunction "2_2") (pintype "passive"))
      (node (ref "C5") (pin "2") (pinfunction "2_2") (pintype "passive"))
      (node (ref "C6") (pin "1") (pinfunction "1_1") (pintype "passive"))
      (node (ref "C7") (pin "2") (pinfunction "2_2") (pintype "passive"))
      (node (ref "C8") (pin "2") (pinfunction "2_2") (pintype "passive"))
      (node (ref "C9") (pin "2") (pinfunction "2_2") (pintype "passive"))
      (node (ref "CONN_CAM") (pin "18") (pinfunction "18_18") (pintype "passive"))
      (node (ref "CONN_CAM") (pin "2") (pinfunction "2_2") (pintype "passive"))
      (node (ref "CONN_MAG") (pin "1") (pinfunction "1_1") (pintype "passive"))
      (node (ref "CONN_RJ45") (pin "9") (pinfunction "9G+_9") (pintype "passive"))
      (node (ref "CONN_RJ45") (pin "P$1") (pinfunction "14GND_P$1") (pintype "passive"))
      (node (ref "CONN_RJ45") (pin "P$2") (pinfunction "13GND_P$2") (pintype "passive"))
      (node (ref "CONN_RJ45") (pin "P8") (pinfunction "8GND_P8") (pintype "passive"))
      (node (ref "IC_ETH1") (pin "22") (pinfunction "GND_22") (pintype "power_in"))
      (node (ref "IC_ETH1") (pin "25") (pinfunction "GND_25") (pintype "power_in"))
      (node (ref "JACK") (pin "2") (pinfunction "2_2") (pintype "passive"))
      (node (ref "JACK") (pin "3") (pinfunction "3_3") (pintype "passive"))
      (node (ref "R17") (pin "2") (pinfunction "2_2") (pintype "passive"))
      (node (ref "R18") (pin "2") (pinfunction "2_2") (pintype "passive"))
      (node (ref "R19") (pin "2") (pinfunction "2_2") (pintype "passive"))
      (node (ref "R5") (pin "2") (pinfunction "2_2") (pintype "passive"))
      (node (ref "T1") (pin "1") (pinfunction "E_1") (pintype "passive"))
      (node (ref "U1") (pin "1") (pinfunction "ADJ/GND_1") (pintype "passive"))
      (node (ref "U2") (pin "24") (pinfunction "VREFL_24") (pintype "power_in"))
      (node (ref "U2") (pin "25") (pinfunction "VSSA_25") (pintype "power_in"))
      (node (ref "U2") (pin "41") (pinfunction "VSS@2_41") (pintype "power_in"))
      (node (ref "U2") (pin "49") (pinfunction "VSS@3_49") (pintype "power_in"))
      (node (ref "U2") (pin "60") (pinfunction "VSS@4_60") (pintype "power_in"))
      (node (ref "U2") (pin "74") (pinfunction "VSS@5_74") (pintype "power_in"))
      (node (ref "U2") (pin "88") (pinfunction "VSS@6_88") (pintype "power_in"))
      (node (ref "U2") (pin "9") (pinfunction "VSS@1_9") (pintype "power_in"))
    )
    (net (code "73") (name "Net-(CONN_MAG-Pad2)") (class "Default")
      (node (ref "CONN_MAG") (pin "2") (pinfunction "2_2") (pintype "passive"))
      (node (ref "R12") (pin "1") (pinfunction "1_1") (pintype "passive"))
    )
    (net (code "74") (name "Net-(CONN_MAG-Pad3)") (class "Default")
      (node (ref "CONN_MAG") (pin "3") (pinfunction "3_3") (pintype "passive"))
      (node (ref "R13") (pin "1") (pinfunction "1_1") (pintype "passive"))
    )
    (net (code "75") (name "Net-(CONN_MAG-Pad4)") (class "Default")
      (node (ref "CONN_MAG") (pin "4") (pinfunction "4_4") (pintype "passive"))
      (node (ref "R14") (pin "2") (pinfunction "2_2") (pintype "passive"))
    )
    (net (code "76") (name "Net-(CONN_RJ45-10G-)") (class "Default")
      (node (ref "CONN_RJ45") (pin "10") (pinfunction "10G-_10") (pintype "passive"))
      (node (ref "R6") (pin "2") (pinfunction "2_2") (pintype "passive"))
    )
    (net (code "77") (name "Net-(CONN_RJ45-11Y-)") (class "Default")
      (node (ref "CONN_RJ45") (pin "11") (pinfunction "11Y-_11") (pintype "passive"))
      (node (ref "R7") (pin "2") (pinfunction "2_2") (pintype "passive"))
    )
    (net (code "78") (name "Net-(CONN_SWD-Pad3)") (class "Default")
      (node (ref "CONN_SWD") (pin "3") (pinfunction "3_3") (pintype "passive"))
      (node (ref "CONN_SWD") (pin "5") (pinfunction "5_5") (pintype "passive"))
    )
    (net (code "79") (name "Net-(D1-K)") (class "Default")
      (node (ref "C4") (pin "1") (pinfunction "1_1") (pintype "passive"))
      (node (ref "D1") (pin "2") (pinfunction "K_2") (pintype "passive"))
      (node (ref "U1") (pin "3") (pinfunction "IN_3") (pintype "power_in"))
    )
    (net (code "80") (name "Net-(D4-A)") (class "Default")
      (node (ref "D4") (pin "1") (pinfunction "A_1") (pintype "passive"))
      (node (ref "RELAY") (pin "A2") (pinfunction "COIL2_A2") (pintype "passive"))
      (node (ref "T1") (pin "3") (pinfunction "C_3") (pintype "passive"))
    )
    (net (code "81") (name "Net-(D12-BLUE(C))") (class "Default")
      (node (ref "D12") (pin "3") (pinfunction "BLUE(C)_3") (pintype "passive"))
      (node (ref "R23") (pin "1") (pinfunction "1_1") (pintype "passive"))
    )
    (net (code "82") (name "Net-(D12-COMMON_ANODE)") (class "Default")
      (node (ref "D12") (pin "2") (pinfunction "COMMON_ANODE_2") (pintype "passive"))
      (node (ref "R22") (pin "1") (pinfunction "1_1") (pintype "passive"))
    )
    (net (code "83") (name "Net-(D12-GREEN(C))") (class "Default")
      (node (ref "D12") (pin "4") (pinfunction "GREEN(C)_4") (pintype "passive"))
      (node (ref "R21") (pin "1") (pinfunction "1_1") (pintype "passive"))
    )
    (net (code "84") (name "Net-(D12-RED(C))") (class "Default")
      (node (ref "D12") (pin "1") (pinfunction "RED(C)_1") (pintype "passive"))
      (node (ref "R20") (pin "1") (pinfunction "1_1") (pintype "passive"))
    )
    (net (code "85") (name "Net-(T1-B)") (class "Default")
      (node (ref "R24") (pin "1") (pinfunction "1_1") (pintype "passive"))
      (node (ref "T1") (pin "2") (pinfunction "B_2") (pintype "passive"))
    )
    (net (code "86") (name "Net-(U2-ETAL32)") (class "Default")
      (node (ref "U2") (pin "29") (pinfunction "ETAL32_29") (pintype "bidirectional"))
      (node (ref "Y2") (pin "1") (pinfunction "1_1") (pintype "passive"))
    )
    (net (code "87") (name "Net-(U2-XTAL32)") (class "Default")
      (node (ref "U2") (pin "28") (pinfunction "XTAL32_28") (pintype "bidirectional"))
      (node (ref "Y2") (pin "2") (pinfunction "10_2") (pintype "passive"))
    )
    (net (code "88") (name "P3V3") (class "Default")
      (node (ref "C17") (pin "2") (pinfunction "2_2") (pintype "passive"))
      (node (ref "C18") (pin "2") (pinfunction "2_2") (pintype "passive"))
      (node (ref "C6") (pin "2") (pinfunction "2_2") (pintype "passive"))
      (node (ref "CONN_RJ45") (pin "12") (pinfunction "12Y+_12") (pintype "passive"))
      (node (ref "D3") (pin "2") (pinfunction "K_2") (pintype "passive"))
      (node (ref "IC_ETH1") (pin "14") (pinfunction "VDDIO_14") (pintype "power_in"))
      (node (ref "R6") (pin "1") (pinfunction "1_1") (pintype "passive"))
      (node (ref "R8") (pin "2") (pinfunction "2_2") (pintype "passive"))
      (node (ref "U2") (pin "22") (pinfunction "VDDA_22") (pintype "power_in"))
      (node (ref "U2") (pin "30") (pinfunction "VBAT_30") (pintype "power_in"))
    )
    (net (code "89") (name "VDDPLL_1.2V") (class "Default")
      (node (ref "C12") (pin "1") (pinfunction "1_1") (pintype "passive"))
      (node (ref "C13") (pin "1") (pinfunction "1_1") (pintype "passive"))
      (node (ref "IC_ETH1") (pin "1") (pinfunction "VDD_1.2_1") (pintype "power_in"))
    )
    (net (code "90") (name "unconnected-(CONN_SWD-Pad7)") (class "Default")
      (node (ref "CONN_SWD") (pin "7") (pinfunction "7_7") (pintype "passive"))
    )
    (net (code "91") (name "unconnected-(CONN_SWD-Pad8)") (class "Default")
      (node (ref "CONN_SWD") (pin "8") (pinfunction "8_8") (pintype "passive"))
    )
    (net (code "92") (name "unconnected-(CONN_SWD-Pad9)") (class "Default")
      (node (ref "CONN_SWD") (pin "9") (pinfunction "9_9") (pintype "passive"))
    )
    (net (code "93") (name "unconnected-(IC_ETH1-INTRP-Pad18)") (class "Default")
      (node (ref "IC_ETH1") (pin "18") (pinfunction "INTRP_18") (pintype "bidirectional"))
    )
    (net (code "94") (name "unconnected-(U2-1_IN5{slash}CMP0_IN5{slash}ADC1_SE18-Pad26)") (class "Default")
      (node (ref "U2") (pin "26") (pinfunction "1_IN5/CMP0_IN5/ADC1_SE18_26") (pintype "bidirectional"))
    )
    (net (code "95") (name "unconnected-(U2-ADC0_DM0{slash}ADC1_DM3-Pad19)") (class "Default")
      (node (ref "U2") (pin "19") (pinfunction "ADC0_DM0/ADC1_DM3_19") (pintype "bidirectional"))
    )
    (net (code "96") (name "unconnected-(U2-ADC0_DM1-Pad15)") (class "Default")
      (node (ref "U2") (pin "15") (pinfunction "ADC0_DM1_15") (pintype "bidirectional"))
    )
    (net (code "97") (name "unconnected-(U2-ADC0_DP0{slash}ADC1_DP3-Pad18)") (class "Default")
      (node (ref "U2") (pin "18") (pinfunction "ADC0_DP0/ADC1_DP3_18") (pintype "bidirectional"))
    )
    (net (code "98") (name "unconnected-(U2-ADC0_DP1-Pad14)") (class "Default")
      (node (ref "U2") (pin "14") (pinfunction "ADC0_DP1_14") (pintype "bidirectional"))
    )
    (net (code "99") (name "unconnected-(U2-ADC1_DM0{slash}ADC0_DM3-Pad21)") (class "Default")
      (node (ref "U2") (pin "21") (pinfunction "ADC1_DM0/ADC0_DM3_21") (pintype "bidirectional"))
    )
    (net (code "100") (name "unconnected-(U2-ADC1_DM1-Pad17)") (class "Default")
      (node (ref "U2") (pin "17") (pinfunction "ADC1_DM1_17") (pintype "bidirectional"))
    )
    (net (code "101") (name "unconnected-(U2-ADC1_DP0{slash}ADC0_DP3-Pad20)") (class "Default")
      (node (ref "U2") (pin "20") (pinfunction "ADC1_DP0/ADC0_DP3_20") (pintype "bidirectional"))
    )
    (net (code "102") (name "unconnected-(U2-ADC1_DP1-Pad16)") (class "Default")
      (node (ref "U2") (pin "16") (pinfunction "ADC1_DP1_16") (pintype "bidirectional"))
    )
    (net (code "103") (name "unconnected-(U2-PTA0-Pad34)") (class "Default")
      (node (ref "U2") (pin "34") (pinfunction "PTA0_34") (pintype "bidirectional"))
    )
    (net (code "104") (name "unconnected-(U2-PTA2-Pad36)") (class "Default")
      (node (ref "U2") (pin "36") (pinfunction "PTA2_36") (pintype "bidirectional"))
    )
    (net (code "105") (name "unconnected-(U2-PTA3-Pad37)") (class "Default")
      (node (ref "U2") (pin "37") (pinfunction "PTA3_37") (pintype "bidirectional"))
    )
    (net (code "106") (name "unconnected-(U2-PTA4-Pad38)") (class "Default")
      (node (ref "U2") (pin "38") (pinfunction "PTA4_38") (pintype "bidirectional"))
    )
    (net (code "107") (name "unconnected-(U2-PTA5-Pad39)") (class "Default")
      (node (ref "U2") (pin "39") (pinfunction "PTA5_39") (pintype "bidirectional"))
    )
    (net (code "108") (name "unconnected-(U2-PTA12-Pad42)") (class "Default")
      (node (ref "U2") (pin "42") (pinfunction "PTA12_42") (pintype "bidirectional"))
    )
    (net (code "109") (name "unconnected-(U2-PTA13{slash}LLWU_P4-Pad43)") (class "Default")
      (node (ref "U2") (pin "43") (pinfunction "PTA13/LLWU_P4_43") (pintype "bidirectional"))
    )
    (net (code "110") (name "unconnected-(U2-PTA14-Pad44)") (class "Default")
      (node (ref "U2") (pin "44") (pinfunction "PTA14_44") (pintype "bidirectional"))
    )
    (net (code "111") (name "unconnected-(U2-PTA15-Pad45)") (class "Default")
      (node (ref "U2") (pin "45") (pinfunction "PTA15_45") (pintype "bidirectional"))
    )
    (net (code "112") (name "unconnected-(U2-PTA16-Pad46)") (class "Default")
      (node (ref "U2") (pin "46") (pinfunction "PTA16_46") (pintype "bidirectional"))
    )
    (net (code "113") (name "unconnected-(U2-PTA17-Pad47)") (class "Default")
      (node (ref "U2") (pin "47") (pinfunction "PTA17_47") (pintype "bidirectional"))
    )
    (net (code "114") (name "unconnected-(U2-PTA18-Pad50)") (class "Default")
      (node (ref "U2") (pin "50") (pinfunction "PTA18_50") (pintype "bidirectional"))
    )
    (net (code "115") (name "unconnected-(U2-PTA19-Pad51)") (class "Default")
      (node (ref "U2") (pin "51") (pinfunction "PTA19_51") (pintype "bidirectional"))
    )
    (net (code "116") (name "unconnected-(U2-PTB0{slash}LLWU_P5-Pad53)") (class "Default")
      (node (ref "U2") (pin "53") (pinfunction "PTB0/LLWU_P5_53") (pintype "bidirectional"))
    )
    (net (code "117") (name "unconnected-(U2-PTB1-Pad54)") (class "Default")
      (node (ref "U2") (pin "54") (pinfunction "PTB1_54") (pintype "bidirectional"))
    )
    (net (code "118") (name "unconnected-(U2-PTB11-Pad59)") (class "Default")
      (node (ref "U2") (pin "59") (pinfunction "PTB11_59") (pintype "bidirectional"))
    )
    (net (code "119") (name "unconnected-(U2-PTB16-Pad62)") (class "Default")
      (node (ref "U2") (pin "62") (pinfunction "PTB16_62") (pintype "bidirectional"))
    )
    (net (code "120") (name "unconnected-(U2-PTB17-Pad63)") (class "Default")
      (node (ref "U2") (pin "63") (pinfunction "PTB17_63") (pintype "bidirectional"))
    )
    (net (code "121") (name "unconnected-(U2-PTB18-Pad64)") (class "Default")
      (node (ref "U2") (pin "64") (pinfunction "PTB18_64") (pintype "bidirectional"))
    )
    (net (code "122") (name "unconnected-(U2-PTB19-Pad65)") (class "Default")
      (node (ref "U2") (pin "65") (pinfunction "PTB19_65") (pintype "bidirectional"))
    )
    (net (code "123") (name "unconnected-(U2-PTB20-Pad66)") (class "Default")
      (node (ref "U2") (pin "66") (pinfunction "PTB20_66") (pintype "bidirectional"))
    )
    (net (code "124") (name "unconnected-(U2-PTB21-Pad67)") (class "Default")
      (node (ref "U2") (pin "67") (pinfunction "PTB21_67") (pintype "bidirectional"))
    )
    (net (code "125") (name "unconnected-(U2-PTB22-Pad68)") (class "Default")
      (node (ref "U2") (pin "68") (pinfunction "PTB22_68") (pintype "bidirectional"))
    )
    (net (code "126") (name "unconnected-(U2-PTB23-Pad69)") (class "Default")
      (node (ref "U2") (pin "69") (pinfunction "PTB23_69") (pintype "bidirectional"))
    )
    (net (code "127") (name "unconnected-(U2-PTC8-Pad80)") (class "Default")
      (node (ref "U2") (pin "80") (pinfunction "PTC8_80") (pintype "bidirectional"))
    )
    (net (code "128") (name "unconnected-(U2-PTC9-Pad81)") (class "Default")
      (node (ref "U2") (pin "81") (pinfunction "PTC9_81") (pintype "bidirectional"))
    )
    (net (code "129") (name "unconnected-(U2-PTC10-Pad82)") (class "Default")
      (node (ref "U2") (pin "82") (pinfunction "PTC10_82") (pintype "bidirectional"))
    )
    (net (code "130") (name "unconnected-(U2-PTC11-Pad83)") (class "Default")
      (node (ref "U2") (pin "83") (pinfunction "PTC11_83") (pintype "bidirectional"))
    )
    (net (code "131") (name "unconnected-(U2-PTC12-Pad84)") (class "Default")
      (node (ref "U2") (pin "84") (pinfunction "PTC12_84") (pintype "bidirectional"))
    )
    (net (code "132") (name "unconnected-(U2-PTC13-Pad85)") (class "Default")
      (node (ref "U2") (pin "85") (pinfunction "PTC13_85") (pintype "bidirectional"))
    )
    (net (code "133") (name "unconnected-(U2-PTC14-Pad86)") (class "Default")
      (node (ref "U2") (pin "86") (pinfunction "PTC14_86") (pintype "bidirectional"))
    )
    (net (code "134") (name "unconnected-(U2-PTC15-Pad87)") (class "Default")
      (node (ref "U2") (pin "87") (pinfunction "PTC15_87") (pintype "bidirectional"))
    )
    (net (code "135") (name "unconnected-(U2-PTC16-Pad90)") (class "Default")
      (node (ref "U2") (pin "90") (pinfunction "PTC16_90") (pintype "bidirectional"))
    )
    (net (code "136") (name "unconnected-(U2-PTC17-Pad91)") (class "Default")
      (node (ref "U2") (pin "91") (pinfunction "PTC17_91") (pintype "bidirectional"))
    )
    (net (code "137") (name "unconnected-(U2-PTC18-Pad92)") (class "Default")
      (node (ref "U2") (pin "92") (pinfunction "PTC18_92") (pintype "bidirectional"))
    )
    (net (code "138") (name "unconnected-(U2-PTD1-Pad94)") (class "Default")
      (node (ref "U2") (pin "94") (pinfunction "PTD1_94") (pintype "bidirectional"))
    )
    (net (code "139") (name "unconnected-(U2-PTD3-Pad96)") (class "Default")
      (node (ref "U2") (pin "96") (pinfunction "PTD3_96") (pintype "bidirectional"))
    )
    (net (code "140") (name "unconnected-(U2-PTD4{slash}LLWU_P14-Pad97)") (class "Default")
      (node (ref "U2") (pin "97") (pinfunction "PTD4/LLWU_P14_97") (pintype "bidirectional"))
    )
    (net (code "141") (name "unconnected-(U2-PTD5-Pad98)") (class "Default")
      (node (ref "U2") (pin "98") (pinfunction "PTD5_98") (pintype "bidirectional"))
    )
    (net (code "142") (name "unconnected-(U2-PTD6{slash}LLWU_P15-Pad99)") (class "Default")
      (node (ref "U2") (pin "99") (pinfunction "PTD6/LLWU_P15_99") (pintype "bidirectional"))
    )
    (net (code "143") (name "unconnected-(U2-PTD7-Pad100)") (class "Default")
      (node (ref "U2") (pin "100") (pinfunction "PTD7_100") (pintype "bidirectional"))
    )
    (net (code "144") (name "unconnected-(U2-PTE26-Pad33)") (class "Default")
      (node (ref "U2") (pin "33") (pinfunction "PTE26_33") (pintype "bidirectional"))
    )
    (net (code "145") (name "unconnected-(U2-RESET+B-Pad52)") (class "Default")
      (node (ref "U2") (pin "52") (pinfunction "RESET+B_52") (pintype "bidirectional"))
    )
    (net (code "146") (name "unconnected-(U2-USB0_DM-Pad11)") (class "Default")
      (node (ref "U2") (pin "11") (pinfunction "USB0_DM_11") (pintype "bidirectional"))
    )
    (net (code "147") (name "unconnected-(U2-USB0_DP-Pad10)") (class "Default")
      (node (ref "U2") (pin "10") (pinfunction "USB0_DP_10") (pintype "bidirectional"))
    )
    (net (code "148") (name "unconnected-(U2-_OUT{slash}CMP1_IN3{slash}ADC0_SE23-Pad27)") (class "Default")
      (node (ref "U2") (pin "27") (pinfunction "_OUT/CMP1_IN3/ADC0_SE23_27") (pintype "bidirectional"))
    )
  )
)
